# PoE.net
KiCad netlist of a schematic drawn in Altium Designer
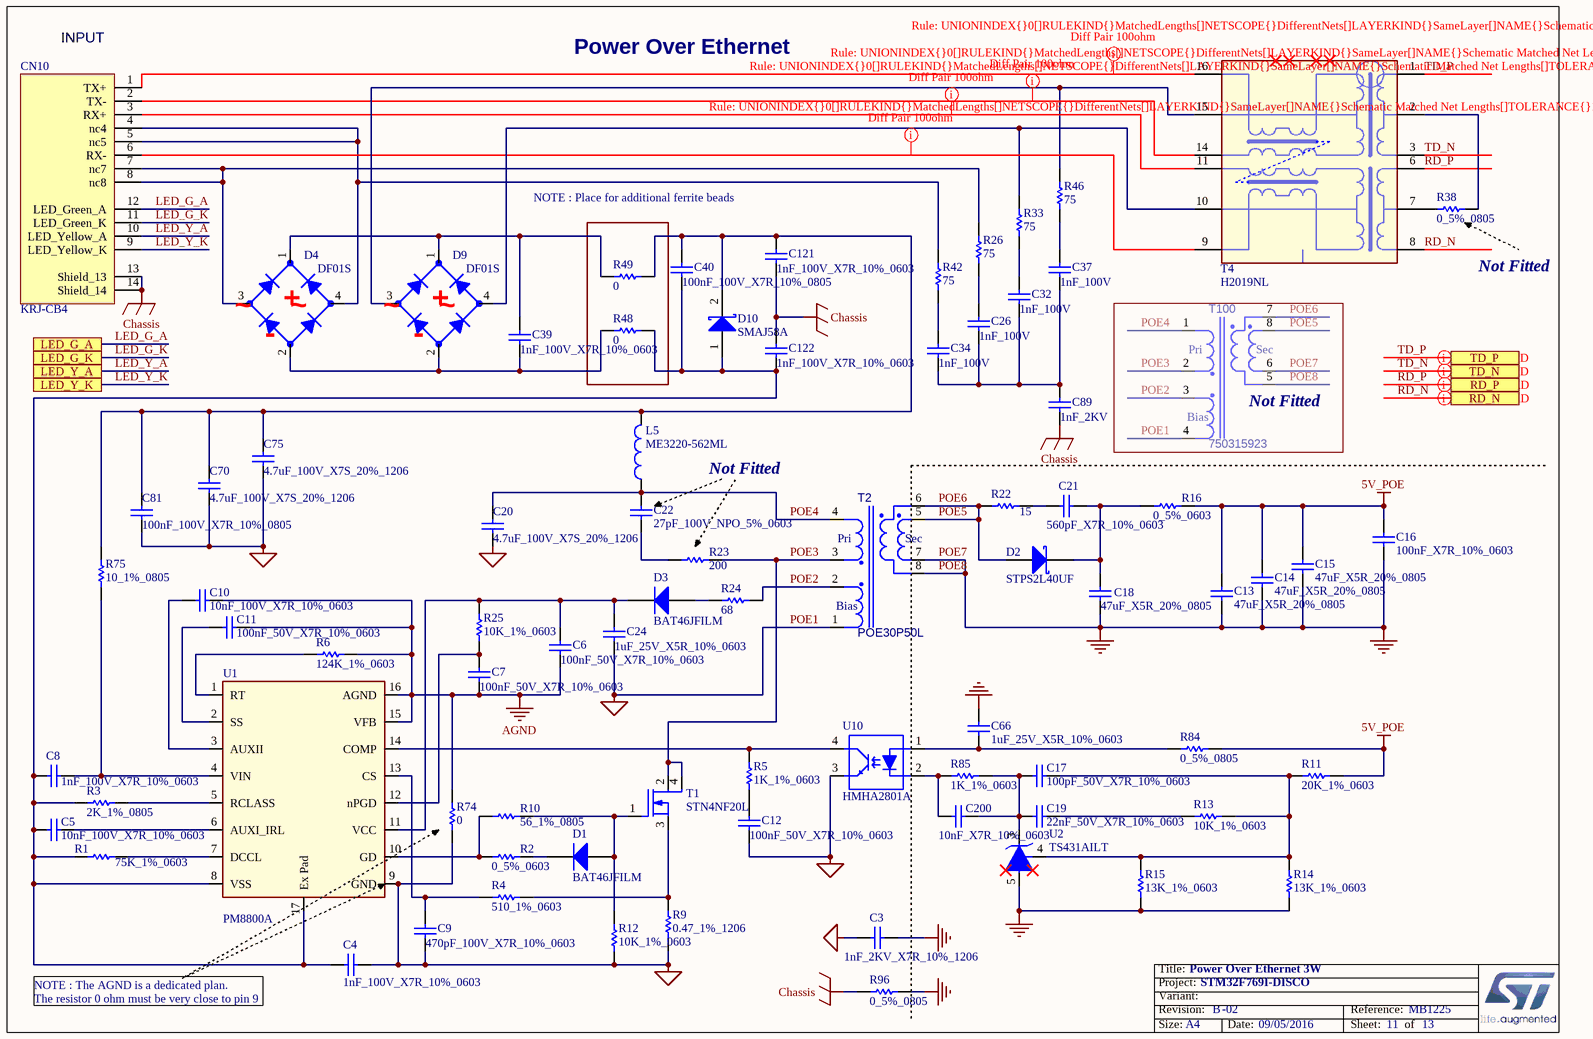
[diagram p0: PoE.SchDoc]

(export (version "E")
  (design (tool "Eeschema 10.0.6"))
  (components
    (comp (ref "C3")
      (value "1nF_2KV_X7R_10%_1206")
      (footprint "1206C")
      (description "Capacitor,1nF,2KV,X7R,10%,1206,YAGEO")
      (libsource (lib "MCD_TOOLS_CAPACITOR") (part "Cap_1nF_2KV_X7R_10%_1206"))
    )
    (comp (ref "C4")
      (value "1nF_100V_X7R_10%_0603")
      (footprint "0603C")
      (description "Capacitor,1nF,100V,X7R,10%,0603,YAGEO")
      (libsource (lib "MCD_TOOLS_CAPACITOR") (part "Cap_1nF_100V_X7R_10%_0603"))
    )
    (comp (ref "C5")
      (value "10nF_100V_X7R_10%_0603")
      (footprint "0603C")
      (description "Capacitor,10nF,100V,X7R,10%,0603,YAGEO")
      (libsource (lib "MCD_TOOLS_CAPACITOR") (part "Cap_10nF_100V_X7R_10%_0603"))
    )
    (comp (ref "C6")
      (value "100nF_50V_X7R_10%_0603")
      (footprint "0603C")
      (description "Capacitor,100nF,50V,X7R,10%,0603,YAGEO")
      (libsource (lib "MCD_TOOLS_CAPACITOR") (part "Cap_100nF_50V_X7R_10%_0603"))
    )
    (comp (ref "C7")
      (value "100nF_50V_X7R_10%_0603")
      (footprint "0603C")
      (description "Capacitor,100nF,50V,X7R,10%,0603,YAGEO")
      (libsource (lib "MCD_TOOLS_CAPACITOR") (part "Cap_100nF_50V_X7R_10%_0603"))
    )
    (comp (ref "C8")
      (value "1nF_100V_X7R_10%_0603")
      (footprint "0603C")
      (description "Capacitor,1nF,100V,X7R,10%,0603,YAGEO")
      (libsource (lib "MCD_TOOLS_CAPACITOR") (part "Cap_1nF_100V_X7R_10%_0603"))
    )
    (comp (ref "C9")
      (value "470pF_100V_X7R_10%_0603")
      (footprint "0603C")
      (description "Capacitor,470pF,100V,X7R,10%,0603,AVX")
      (libsource (lib "MCD_TOOLS_CAPACITOR") (part "Cap_470pF_100V_X7R_10%_0603"))
    )
    (comp (ref "C10")
      (value "10nF_100V_X7R_10%_0603")
      (footprint "0603C")
      (description "Capacitor,10nF,100V,X7R,10%,0603,YAGEO")
      (libsource (lib "MCD_TOOLS_CAPACITOR") (part "Cap_10nF_100V_X7R_10%_0603"))
    )
    (comp (ref "C11")
      (value "100nF_50V_X7R_10%_0603")
      (footprint "0603C")
      (description "Capacitor,100nF,50V,X7R,10%,0603,YAGEO")
      (libsource (lib "MCD_TOOLS_CAPACITOR") (part "Cap_100nF_50V_X7R_10%_0603"))
    )
    (comp (ref "C12")
      (value "100nF_50V_X7R_10%_0603")
      (footprint "0603C")
      (description "Capacitor,100nF,50V,X7R,10%,0603,YAGEO")
      (libsource (lib "MCD_TOOLS_CAPACITOR") (part "Cap_100nF_50V_X7R_10%_0603"))
    )
    (comp (ref "C13")
      (value "47uF_X5R_20%_0805")
      (footprint "0805C")
      (description "Capacitor,47uF,10V,X5R,20%,0805,MURATA")
      (libsource (lib "MCD_TOOLS_CAPACITOR") (part "Cap_47uF_X5R_20%_0805"))
    )
    (comp (ref "C14")
      (value "47uF_X5R_20%_0805")
      (footprint "0805C")
      (description "Capacitor,47uF,10V,X5R,20%,0805,MURATA")
      (libsource (lib "MCD_TOOLS_CAPACITOR") (part "Cap_47uF_X5R_20%_0805"))
    )
    (comp (ref "C15")
      (value "47uF_X5R_20%_0805")
      (footprint "0805C")
      (description "Capacitor,47uF,10V,X5R,20%,0805,MURATA")
      (libsource (lib "MCD_TOOLS_CAPACITOR") (part "Cap_47uF_X5R_20%_0805"))
    )
    (comp (ref "C16")
      (value "100nF_X7R_10%_0603")
      (footprint "0603C")
      (description "Capacitor,100nF,16V,X7R,10%,0603,YAGEO")
      (libsource (lib "MCD_TOOLS_CAPACITOR") (part "Cap_100nF_X7R_10%_0603"))
    )
    (comp (ref "C17")
      (value "100pF_50V_X7R_10%_0603")
      (footprint "0603C")
      (description "Capacitor,100pF,50V,X7R,10%,0603,AVX")
      (libsource (lib "MCD_TOOLS_CAPACITOR") (part "Cap_100pF_50V_X7R_10%_0603"))
    )
    (comp (ref "C18")
      (value "47uF_X5R_20%_0805")
      (footprint "0805C")
      (description "Capacitor,47uF,10V,X5R,20%,0805,MURATA")
      (libsource (lib "MCD_TOOLS_CAPACITOR") (part "Cap_47uF_X5R_20%_0805"))
    )
    (comp (ref "C19")
      (value "22nF_50V_X7R_10%_0603")
      (footprint "0603C")
      (description "Capacitor,22nF,50V,X7R,10%,0603,YAGEO")
      (libsource (lib "MCD_TOOLS_CAPACITOR") (part "Cap_22nF_50V_X7R_10%_0603"))
    )
    (comp (ref "C20")
      (value "4.7uF_100V_X7S_20%_1206")
      (footprint "1206C")
      (description "Capacitor,4.7uF,100V, X7S,20%,1206,AVX")
      (libsource (lib "MCD_TOOLS_CAPACITOR") (part "Cap_4.7uF_100V_X7S_20%_1206"))
    )
    (comp (ref "C21")
      (value "560pF_X7R_10%_0603")
      (footprint "0603C")
      (description "Capacitor,560pF,16V,X7R,10%,0603,AVX")
      (libsource (lib "MCD_TOOLS_CAPACITOR") (part "Cap_560pF_X7R_10%_0603"))
    )
    (comp (ref "C22")
      (value "27pF_100V_NPO_5%_0603")
      (footprint "0603C")
      (description "Capacitor,27pF,100V,NPO,5%,0603,YAGEO")
      (libsource (lib "MCD_TOOLS_CAPACITOR") (part "Cap_27pF_100V_NPO_5%_0603"))
    )
    (comp (ref "C24")
      (value "1uF_25V_X5R_10%_0603")
      (footprint "0603C")
      (description "Capacitor,1uF,25V,X5R,10%,0603,YAGEO")
      (libsource (lib "MCD_TOOLS_CAPACITOR") (part "Cap_1uF_25V_X5R_10%_0603"))
    )
    (comp (ref "C26")
      (value "1nF_100V")
      (footprint "0603C")
      (description "Capacitor,1nF,100V,X7R,10%,0603,YAGEO")
      (libsource (lib "MCD_TOOLS_CAPACITOR") (part "Cap_1nF_100V_X7R_10%_0603"))
    )
    (comp (ref "C32")
      (value "1nF_100V")
      (footprint "0603C")
      (description "Capacitor,1nF,100V,X7R,10%,0603,YAGEO")
      (libsource (lib "MCD_TOOLS_CAPACITOR") (part "Cap_1nF_100V_X7R_10%_0603"))
    )
    (comp (ref "C34")
      (value "1nF_100V")
      (footprint "0603C")
      (description "Capacitor,1nF,100V,X7R,10%,0603,YAGEO")
      (libsource (lib "MCD_TOOLS_CAPACITOR") (part "Cap_1nF_100V_X7R_10%_0603"))
    )
    (comp (ref "C37")
      (value "1nF_100V")
      (footprint "0603C")
      (description "Capacitor,1nF,100V,X7R,10%,0603,YAGEO")
      (libsource (lib "MCD_TOOLS_CAPACITOR") (part "Cap_1nF_100V_X7R_10%_0603"))
    )
    (comp (ref "C39")
      (value "1nF_100V_X7R_10%_0603")
      (footprint "0603C")
      (description "Capacitor,1nF,100V,X7R,10%,0603,YAGEO")
      (libsource (lib "MCD_TOOLS_CAPACITOR") (part "Cap_1nF_100V_X7R_10%_0603"))
    )
    (comp (ref "C40")
      (value "100nF_100V_X7R_10%_0805")
      (footprint "0805C")
      (description "Capacitor,100nF,100V,X7R,10%,0805,TDK")
      (libsource (lib "MCD_TOOLS_CAPACITOR") (part "Cap_100nF_100V_X7R_10%_0805"))
    )
    (comp (ref "C66")
      (value "1uF_25V_X5R_10%_0603")
      (footprint "0603C")
      (description "Capacitor,1uF,25V,X5R,10%,0603,YAGEO")
      (libsource (lib "MCD_TOOLS_CAPACITOR") (part "Cap_1uF_25V_X5R_10%_0603"))
    )
    (comp (ref "C70")
      (value "4.7uF_100V_X7S_20%_1206")
      (footprint "1206C")
      (description "Capacitor,4.7uF,100V, X7S,20%,1206,AVX")
      (libsource (lib "MCD_TOOLS_CAPACITOR") (part "Cap_4.7uF_100V_X7S_20%_1206"))
    )
    (comp (ref "C75")
      (value "4.7uF_100V_X7S_20%_1206")
      (footprint "1206C")
      (description "Capacitor,4.7uF,100V, X7S,20%,1206,AVX")
      (libsource (lib "MCD_TOOLS_CAPACITOR") (part "Cap_4.7uF_100V_X7S_20%_1206"))
    )
    (comp (ref "C81")
      (value "100nF_100V_X7R_10%_0805")
      (footprint "0805C")
      (description "Capacitor,100nF,100V,X7R,10%,0805,TDK")
      (libsource (lib "MCD_TOOLS_CAPACITOR") (part "Cap_100nF_100V_X7R_10%_0805"))
    )
    (comp (ref "C89")
      (value "1nF_2KV")
      (footprint "1206C")
      (description "Capacitor,1nF,2KV,X7R,10%,1206,YAGEO")
      (libsource (lib "MCD_TOOLS_CAPACITOR") (part "Cap_1nF_2KV_X7R_10%_1206"))
    )
    (comp (ref "C121")
      (value "1nF_100V_X7R_10%_0603")
      (footprint "0603C")
      (description "Capacitor,1nF,100V,X7R,10%,0603,YAGEO")
      (libsource (lib "MCD_TOOLS_CAPACITOR") (part "Cap_1nF_100V_X7R_10%_0603"))
    )
    (comp (ref "C122")
      (value "1nF_100V_X7R_10%_0603")
      (footprint "0603C")
      (description "Capacitor,1nF,100V,X7R,10%,0603,YAGEO")
      (libsource (lib "MCD_TOOLS_CAPACITOR") (part "Cap_1nF_100V_X7R_10%_0603"))
    )
    (comp (ref "C200")
      (value "10nF_X7R_10%_0603")
      (footprint "0603C")
      (description "Capacitor,10nF,50V,X7R,10%,0603,YAGEO")
      (libsource (lib "MCD_TOOLS_CAPACITOR") (part "Cap_10nF_X7R_10%_0603"))
    )
    (comp (ref "CN10")
      (value "KRJ-CB4")
      (footprint "RJ45_LED_KRJ-CB4R2GYZNL_EM")
      (description "100 Base-TX (Fast Ethernet)  RJ45 single port (1x1) with LEDS Integrated Connector")
      (libsource (lib "MCD_TOOLS_CONNECTOR") (part "KRJ-CB4"))
    )
    (comp (ref "D1")
      (value "BAT46JFILM")
      (footprint "SOD-323")
      (description "Schottky Single diode(150mA, 100V)")
      (libsource (lib "MCD_TOOLS_MISCELLANEOUS") (part "BAT46JFILM"))
    )
    (comp (ref "D2")
      (value "STPS2L40UF")
      (footprint "SMB")
      (description "Low drop power Schottky rectifier(2A, 40V, 0.34V)")
      (libsource (lib "MCD_TOOLS_MISCELLANEOUS") (part "STPS2L40UF"))
    )
    (comp (ref "D3")
      (value "BAT46JFILM")
      (footprint "SOD-323")
      (description "Schottky Single diode(150mA, 100V)")
      (libsource (lib "MCD_TOOLS_MISCELLANEOUS") (part "BAT46JFILM"))
    )
    (comp (ref "D4")
      (value "DF01S")
      (footprint "DBS101-107G")
      (description "Surface Mount Bridge Rectifiers")
      (libsource (lib "MCD_TOOLS_MISCELLANEOUS") (part "DF01S_SMD"))
    )
    (comp (ref "D9")
      (value "DF01S")
      (footprint "DBS101-107G")
      (description "Surface Mount Bridge Rectifiers")
      (libsource (lib "MCD_TOOLS_MISCELLANEOUS") (part "DF01S_SMD"))
    )
    (comp (ref "D10")
      (value "SMAJ58A")
      (footprint "SMA")
      (description "Transil 400W, VRM=58V")
      (libsource (lib "MCD_TOOLS_MISCELLANEOUS") (part "SMAJ58A"))
    )
    (comp (ref "L5")
      (value "ME3220-562ML")
      (footprint "LSM2_3R2X2R8_H2")
      (description "Power Inductor, 5.6uH, 0.2R, ME3220-562ML, CoilCraft")
      (libsource (lib "MCD_TOOLS_MISCELLANEOUS") (part "ME3220-562ML"))
    )
    (comp (ref "R1")
      (value "75K_1%_0603")
      (footprint "0603R")
      (description "Resistor,75K,0603,1%,YAGEO")
      (libsource (lib "MCD_TOOLS_RESISTOR") (part "Res_75K_1%_0603"))
    )
    (comp (ref "R2")
      (value "0_5%_0603")
      (footprint "0603R-GS")
      (description "Resistor,0,0603,5%,YAGEO")
      (libsource (lib "MCD_TOOLS_RESISTOR") (part "Res_0_5%_0603"))
    )
    (comp (ref "R3")
      (value "2K_1%_0805")
      (footprint "0805R")
      (description "Resistor,2K,0805,1%,YAGEO")
      (libsource (lib "MCD_TOOLS_RESISTOR") (part "Res_2K_1%_0805"))
    )
    (comp (ref "R4")
      (value "510_1%_0603")
      (footprint "0603R")
      (description "Resistor,510,0603,1%,YAGEO")
      (libsource (lib "MCD_TOOLS_RESISTOR") (part "Res_510_1%_0603"))
    )
    (comp (ref "R5")
      (value "1K_1%_0603")
      (footprint "0603R")
      (description "Resistor,1K,0603,1%,YAGEO")
      (libsource (lib "MCD_TOOLS_RESISTOR") (part "Res_1K_1%_0603"))
    )
    (comp (ref "R6")
      (value "124K_1%_0603")
      (footprint "0603R")
      (description "Resistor,124K,0603,1%,YAGEO")
      (libsource (lib "MCD_TOOLS_RESISTOR") (part "Res_124K_1%_0603"))
    )
    (comp (ref "R9")
      (value "0.47_1%_1206")
      (footprint "1206R")
      (description "Resistor,0.47,1206,1%,YAGEO")
      (libsource (lib "MCD_TOOLS_RESISTOR") (part "Res_0.47_1%_1206"))
    )
    (comp (ref "R10")
      (value "56_1%_0805")
      (footprint "0805R")
      (description "Resistor,56,0805,1%,YAGEO")
      (libsource (lib "MCD_TOOLS_RESISTOR") (part "Res_56_1%_0805"))
    )
    (comp (ref "R11")
      (value "20K_1%_0603")
      (footprint "0603R")
      (description "Resistor,20K,0603,1%,YAGEO")
      (libsource (lib "MCD_TOOLS_RESISTOR") (part "Res_20K_1%_0603"))
    )
    (comp (ref "R12")
      (value "10K_1%_0603")
      (footprint "0603R")
      (description "Resistor,10K,0603,1%,YAGEO")
      (libsource (lib "MCD_TOOLS_RESISTOR") (part "Res_10K_1%_0603"))
    )
    (comp (ref "R13")
      (value "10K_1%_0603")
      (footprint "0603R")
      (description "Resistor,10K,0603,1%,YAGEO")
      (libsource (lib "MCD_TOOLS_RESISTOR") (part "Res_10K_1%_0603"))
    )
    (comp (ref "R14")
      (value "13K_1%_0603")
      (footprint "0603R")
      (description "Resistor,13K,0603,1%,YAGEO")
      (libsource (lib "MCD_TOOLS_RESISTOR") (part "Res_13K_1%_0603"))
    )
    (comp (ref "R15")
      (value "13K_1%_0603")
      (footprint "0603R")
      (description "Resistor,13K,0603,1%,YAGEO")
      (libsource (lib "MCD_TOOLS_RESISTOR") (part "Res_13K_1%_0603"))
    )
    (comp (ref "R16")
      (value "0_5%_0603")
      (footprint "0603R-GS")
      (description "Resistor,0,0603,5%,YAGEO")
      (libsource (lib "MCD_TOOLS_RESISTOR") (part "Res_0_5%_0603"))
    )
    (comp (ref "R22")
      (value "15")
      (footprint "0805R")
      (description "Resistor,15,0805,1%,YAGEO")
      (libsource (lib "MCD_TOOLS_RESISTOR") (part "Res_15_1%_0805"))
    )
    (comp (ref "R23")
      (value "200")
      (footprint "1206R")
      (description "Resistor,200,1206,1%,Rohm")
      (libsource (lib "MCD_TOOLS_RESISTOR") (part "Res_200_1%_1206"))
    )
    (comp (ref "R24")
      (value "68")
      (footprint "0805R")
      (description "Resistor,68,0805,1%,YAGEO")
      (libsource (lib "MCD_TOOLS_RESISTOR") (part "Res_68_1%_0805"))
    )
    (comp (ref "R25")
      (value "10K_1%_0603")
      (footprint "0603R")
      (description "Resistor,10K,0603,1%,YAGEO")
      (libsource (lib "MCD_TOOLS_RESISTOR") (part "Res_10K_1%_0603"))
    )
    (comp (ref "R26")
      (value "75")
      (footprint "0805R")
      (description "Resistor,75,0805,1%,YAGEO")
      (libsource (lib "MCD_TOOLS_RESISTOR") (part "Res_75_1%_0805"))
    )
    (comp (ref "R33")
      (value "75")
      (footprint "0805R")
      (description "Resistor,75,0805,1%,YAGEO")
      (libsource (lib "MCD_TOOLS_RESISTOR") (part "Res_75_1%_0805"))
    )
    (comp (ref "R38")
      (value "0_5%_0805")
      (footprint "0805R")
      (description "Resistor,0,0805,5%,YAGEO")
      (libsource (lib "MCD_TOOLS_RESISTOR") (part "Res_0_5%_0805"))
    )
    (comp (ref "R42")
      (value "75")
      (footprint "0805R")
      (description "Resistor,75,0805,1%,YAGEO")
      (libsource (lib "MCD_TOOLS_RESISTOR") (part "Res_75_1%_0805"))
    )
    (comp (ref "R46")
      (value "75")
      (footprint "0805R")
      (description "Resistor,75,0805,1%,YAGEO")
      (libsource (lib "MCD_TOOLS_RESISTOR") (part "Res_75_1%_0805"))
    )
    (comp (ref "R48")
      (value "0")
      (footprint "0805R")
      (description "Resistor,0,0805,5%,YAGEO")
      (libsource (lib "MCD_TOOLS_RESISTOR") (part "Res_0_5%_0805"))
    )
    (comp (ref "R49")
      (value "0")
      (footprint "0805R")
      (description "Resistor,0,0805,5%,YAGEO")
      (libsource (lib "MCD_TOOLS_RESISTOR") (part "Res_0_5%_0805"))
    )
    (comp (ref "R74")
      (value "0")
      (footprint "0603R-GS")
      (description "Resistor,0,0603,5%,YAGEO")
      (libsource (lib "MCD_TOOLS_RESISTOR") (part "Res_0_5%_0603"))
    )
    (comp (ref "R75")
      (value "10_1%_0805")
      (footprint "0805R")
      (description "Resistor,10,0805,1%,Stackpole,1/4W")
      (libsource (lib "MCD_TOOLS_RESISTOR") (part "Res_10_1%_0805"))
    )
    (comp (ref "R84")
      (value "0_5%_0805")
      (footprint "0805R")
      (description "Resistor,0,0805,5%,YAGEO")
      (libsource (lib "MCD_TOOLS_RESISTOR") (part "Res_0_5%_0805"))
    )
    (comp (ref "R85")
      (value "1K_1%_0603")
      (footprint "0603R")
      (description "Resistor,1K,0603,1%,YAGEO")
      (libsource (lib "MCD_TOOLS_RESISTOR") (part "Res_1K_1%_0603"))
    )
    (comp (ref "R96")
      (value "0_5%_0805")
      (footprint "0805R")
      (description "Resistor,0,0805,5%,YAGEO")
      (libsource (lib "MCD_TOOLS_RESISTOR") (part "Res_0_5%_0805"))
    )
    (comp (ref "T1")
      (value "STN4NF20L")
      (footprint "SOT-223")
      (description "N-channel 200 V, 1.1ohm, 1 A, low gate charge STripFET II, Power MOSFET")
      (libsource (lib "MCD_TOOLS_MISCELLANEOUS") (part "STN4NF20L"))
    )
    (comp (ref "T2")
      (value "POE30P50L")
      (footprint "TF_10R9X13R2-12R2X14R4_CPT")
      (description "Flyback Transformers for 3 Watt, PoE applications, CoilCraft Cyntec")
      (fields (field (name "PROVIDED") "Sub Co"))
      (libsource (lib "MCD_TOOLS_MISCELLANEOUS") (part "POE30P_C"))
    )
    (comp (ref "T4")
      (value "H2019NL")
      (footprint "TF_16SM_12R7X9R65")
      (description "10/100BASE-TX VoIP Magnetics Modules, Data Transformer")
      (libsource (lib "MCD_TOOLS_MISCELLANEOUS") (part "H2019"))
    )
    (comp (ref "T100")
      (value "750315923")
      (footprint "TF_8SM_12R04X12R85")
      (description "Flyback Transformers for 3 Watt, PoE applications, Wurth")
      (fields (field (name "PROVIDED") "Sub Co"))
      (libsource (lib "MCD_TOOLS_MISCELLANEOUS") (part "POE30P_W"))
    )
    (comp (ref "U1")
      (value "PM8800A")
      (footprint "TSSOP16_0R65_5x6R4_TP")
      (fields (field (name "PROVIDED") "STM"))
      (libsource (lib "MCD_TOOLS_MISCELLANEOUS") (part "PM8800A"))
    )
    (comp (ref "U2")
      (value "TS431AILT")
      (footprint "SOT23-5")
      (description "Low voltage adjustable shunt reference")
      (libsource (lib "MCD_TOOLS_MISCELLANEOUS") (part "TS431AILT"))
    )
    (comp (ref "U10")
      (value "HMHA2801A")
      (footprint "PC_4SM_1R27_2R5X6R8")
      (description "OPTOISOLATOR 3.7KV TRANSISTOR 4SMD")
      (libsource (lib "MCD_TOOLS_MISCELLANEOUS") (part "HMHA2801A"))
    )
  )
  (nets
    (net (code "1") (name "/LED_G_A") (class "Default")
      (node (ref "CN10") (pin "12") (pinfunction "LED_Green_A_12") (pintype "passive"))
    )
    (net (code "2") (name "/LED_G_K") (class "Default")
      (node (ref "CN10") (pin "11") (pinfunction "LED_Green_K_11") (pintype "passive"))
    )
    (net (code "3") (name "/LED_Y_A") (class "Default")
      (node (ref "CN10") (pin "10") (pinfunction "LED_Yellow_A_10") (pintype "passive"))
    )
    (net (code "4") (name "/LED_Y_K") (class "Default")
      (node (ref "CN10") (pin "9") (pinfunction "LED_Yellow_K_9") (pintype "passive"))
    )
    (net (code "5") (name "/POE2") (class "Default")
      (node (ref "R24") (pin "2") (pinfunction "2_2") (pintype "passive"))
      (node (ref "T100") (pin "3") (pinfunction "3_3") (pintype "passive"))
      (node (ref "T2") (pin "2") (pinfunction "2_2") (pintype "passive"))
    )
    (net (code "6") (name "/POE3") (class "Default")
      (node (ref "R23") (pin "2") (pinfunction "2_2") (pintype "passive"))
      (node (ref "T1") (pin "2") (pinfunction "D_2") (pintype "passive"))
      (node (ref "T1") (pin "4") (pinfunction "D_4") (pintype "passive"))
      (node (ref "T100") (pin "2") (pinfunction "2_2") (pintype "passive"))
      (node (ref "T2") (pin "3") (pinfunction "3_3") (pintype "passive"))
    )
    (net (code "7") (name "/POE4") (class "Default")
      (node (ref "C20") (pin "2") (pinfunction "2_2") (pintype "passive"))
      (node (ref "C22") (pin "2") (pinfunction "2_2") (pintype "passive"))
      (node (ref "L5") (pin "1") (pinfunction "1_1") (pintype "passive"))
      (node (ref "T100") (pin "1") (pinfunction "1_1") (pintype "passive"))
      (node (ref "T2") (pin "4") (pinfunction "4_4") (pintype "passive"))
    )
    (net (code "8") (name "/POE5") (class "Default")
      (node (ref "D2") (pin "1") (pinfunction "A_1") (pintype "passive"))
      (node (ref "R22") (pin "1") (pinfunction "1_1") (pintype "passive"))
      (node (ref "T100") (pin "7") (pinfunction "7_7") (pintype "passive"))
      (node (ref "T100") (pin "8") (pinfunction "8_8") (pintype "passive"))
      (node (ref "T2") (pin "5") (pinfunction "5_5") (pintype "passive"))
      (node (ref "T2") (pin "6") (pinfunction "6_6") (pintype "passive"))
    )
    (net (code "9") (name "/RD_N") (class "Default")
      (node (ref "T4") (pin "8") (pinfunction "rd-_8") (pintype "passive"))
    )
    (net (code "10") (name "/RD_P") (class "Default")
      (node (ref "T4") (pin "6") (pinfunction "rd+_6") (pintype "passive"))
    )
    (net (code "11") (name "/TD_N") (class "Default")
      (node (ref "T4") (pin "3") (pinfunction "td-_3") (pintype "passive"))
    )
    (net (code "12") (name "/TD_P") (class "Default")
      (node (ref "T4") (pin "1") (pinfunction "td+_1") (pintype "passive"))
    )
    (net (code "13") (name "5V_POE") (class "Default")
      (node (ref "C13") (pin "2") (pinfunction "2_2") (pintype "passive"))
      (node (ref "C14") (pin "2") (pinfunction "2_2") (pintype "passive"))
      (node (ref "C15") (pin "2") (pinfunction "2_2") (pintype "passive"))
      (node (ref "C16") (pin "2") (pinfunction "2_2") (pintype "passive"))
      (node (ref "R11") (pin "2") (pinfunction "2_2") (pintype "passive"))
      (node (ref "R16") (pin "2") (pinfunction "2_2") (pintype "passive"))
      (node (ref "R84") (pin "2") (pinfunction "2_2") (pintype "passive"))
    )
    (net (code "14") (name "AGND") (class "Default")
      (node (ref "C10") (pin "2") (pinfunction "2_2") (pintype "passive"))
      (node (ref "C11") (pin "2") (pinfunction "2_2") (pintype "passive"))
      (node (ref "C6") (pin "1") (pinfunction "1_1") (pintype "passive"))
      (node (ref "C7") (pin "1") (pinfunction "1_1") (pintype "passive"))
      (node (ref "R6") (pin "2") (pinfunction "2_2") (pintype "passive"))
      (node (ref "R74") (pin "2") (pinfunction "2_2") (pintype "passive"))
      (node (ref "U1") (pin "15") (pinfunction "VFB_15") (pintype "passive"))
      (node (ref "U1") (pin "16") (pinfunction "AGND_16") (pintype "passive"))
    )
    (net (code "15") (name "Chassis") (class "Default")
      (node (ref "C121") (pin "1") (pinfunction "1_1") (pintype "passive"))
      (node (ref "C122") (pin "2") (pinfunction "2_2") (pintype "passive"))
      (node (ref "C89") (pin "1") (pinfunction "1_1") (pintype "passive"))
      (node (ref "CN10") (pin "13") (pinfunction "Shield_13_13") (pintype "passive"))
      (node (ref "CN10") (pin "14") (pinfunction "Shield_14_14") (pintype "passive"))
      (node (ref "R96") (pin "1") (pinfunction "1_1") (pintype "passive"))
    )
    (net (code "16") (name "GND") (class "Default")
      (node (ref "C13") (pin "1") (pinfunction "1_1") (pintype "passive"))
      (node (ref "C14") (pin "1") (pinfunction "1_1") (pintype "passive"))
      (node (ref "C15") (pin "1") (pinfunction "1_1") (pintype "passive"))
      (node (ref "C16") (pin "1") (pinfunction "1_1") (pintype "passive"))
      (node (ref "C18") (pin "1") (pinfunction "1_1") (pintype "passive"))
      (node (ref "C3") (pin "2") (pinfunction "2_2") (pintype "passive"))
      (node (ref "C66") (pin "2") (pinfunction "2_2") (pintype "passive"))
      (node (ref "R14") (pin "1") (pinfunction "1_1") (pintype "passive"))
      (node (ref "R15") (pin "1") (pinfunction "1_1") (pintype "passive"))
      (node (ref "R96") (pin "2") (pinfunction "2_2") (pintype "passive"))
      (node (ref "T100") (pin "5") (pinfunction "5_5") (pintype "passive"))
      (node (ref "T100") (pin "6") (pinfunction "6_6") (pintype "passive"))
      (node (ref "T2") (pin "7") (pinfunction "7_7") (pintype "passive"))
      (node (ref "T2") (pin "8") (pinfunction "8_8") (pintype "passive"))
      (node (ref "U2") (pin "5") (pinfunction "A_5") (pintype "passive"))
    )
    (net (code "17") (name "GND_POWER_IN") (class "Default")
      (node (ref "C12") (pin "1") (pinfunction "1_1") (pintype "passive"))
      (node (ref "C20") (pin "1") (pinfunction "1_1") (pintype "passive"))
      (node (ref "C24") (pin "1") (pinfunction "1_1") (pintype "passive"))
      (node (ref "C3") (pin "1") (pinfunction "1_1") (pintype "passive"))
      (node (ref "C4") (pin "2") (pinfunction "2_2") (pintype "passive"))
      (node (ref "C70") (pin "1") (pinfunction "1_1") (pintype "passive"))
      (node (ref "C75") (pin "1") (pinfunction "1_1") (pintype "passive"))
      (node (ref "C81") (pin "1") (pinfunction "1_1") (pintype "passive"))
      (node (ref "C9") (pin "1") (pinfunction "1_1") (pintype "passive"))
      (node (ref "R12") (pin "1") (pinfunction "1_1") (pintype "passive"))
      (node (ref "R74") (pin "1") (pinfunction "1_1") (pintype "passive"))
      (node (ref "R9") (pin "1") (pinfunction "1_1") (pintype "passive"))
      (node (ref "T100") (pin "4") (pinfunction "4_4") (pintype "passive"))
      (node (ref "T2") (pin "1") (pinfunction "1_1") (pintype "passive"))
      (node (ref "U1") (pin "9") (pinfunction "GND_9") (pintype "passive"))
      (node (ref "U10") (pin "3") (pinfunction "Emitter_3") (pintype "passive"))
    )
    (net (code "18") (name "Net-(C12-Pad2)") (class "Default")
      (node (ref "C12") (pin "2") (pinfunction "2_2") (pintype "passive"))
      (node (ref "R5") (pin "1") (pinfunction "1_1") (pintype "passive"))
    )
    (net (code "19") (name "Net-(C19-Pad2)") (class "Default")
      (node (ref "C19") (pin "2") (pinfunction "2_2") (pintype "passive"))
      (node (ref "R13") (pin "1") (pinfunction "1_1") (pintype "passive"))
    )
    (net (code "20") (name "Net-(C21-Pad1)") (class "Default")
      (node (ref "C21") (pin "1") (pinfunction "1_1") (pintype "passive"))
      (node (ref "R22") (pin "2") (pinfunction "2_2") (pintype "passive"))
    )
    (net (code "21") (name "Net-(C22-Pad1)") (class "Default")
      (node (ref "C22") (pin "1") (pinfunction "1_1") (pintype "passive"))
      (node (ref "R23") (pin "1") (pinfunction "1_1") (pintype "passive"))
    )
    (net (code "22") (name "Net-(C26-Pad1)") (class "Default")
      (node (ref "C26") (pin "1") (pinfunction "1_1") (pintype "passive"))
      (node (ref "C32") (pin "1") (pinfunction "1_1") (pintype "passive"))
      (node (ref "C34") (pin "1") (pinfunction "1_1") (pintype "passive"))
      (node (ref "C37") (pin "1") (pinfunction "1_1") (pintype "passive"))
      (node (ref "C89") (pin "2") (pinfunction "2_2") (pintype "passive"))
    )
    (net (code "23") (name "Net-(C26-Pad2)") (class "Default")
      (node (ref "C26") (pin "2") (pinfunction "2_2") (pintype "passive"))
      (node (ref "R26") (pin "1") (pinfunction "1_1") (pintype "passive"))
    )
    (net (code "24") (name "Net-(C32-Pad2)") (class "Default")
      (node (ref "C32") (pin "2") (pinfunction "2_2") (pintype "passive"))
      (node (ref "R33") (pin "1") (pinfunction "1_1") (pintype "passive"))
    )
    (net (code "25") (name "Net-(C34-Pad2)") (class "Default")
      (node (ref "C34") (pin "2") (pinfunction "2_2") (pintype "passive"))
      (node (ref "R42") (pin "1") (pinfunction "1_1") (pintype "passive"))
    )
    (net (code "26") (name "Net-(C37-Pad2)") (class "Default")
      (node (ref "C37") (pin "2") (pinfunction "2_2") (pintype "passive"))
      (node (ref "R46") (pin "1") (pinfunction "1_1") (pintype "passive"))
    )
    (net (code "27") (name "Net-(CN10-RX+)") (class "Default")
      (node (ref "CN10") (pin "3") (pinfunction "RX+_3") (pintype "passive"))
      (node (ref "T4") (pin "11") (pinfunction "rx1+_11") (pintype "passive"))
    )
    (net (code "28") (name "Net-(CN10-RX-)") (class "Default")
      (node (ref "CN10") (pin "6") (pinfunction "RX-_6") (pintype "passive"))
      (node (ref "T4") (pin "9") (pinfunction "rx-_9") (pintype "passive"))
    )
    (net (code "29") (name "Net-(CN10-TX+)") (class "Default")
      (node (ref "CN10") (pin "1") (pinfunction "TX+_1") (pintype "passive"))
      (node (ref "T4") (pin "16") (pinfunction "tx1+_16") (pintype "passive"))
    )
    (net (code "30") (name "Net-(CN10-TX-)") (class "Default")
      (node (ref "CN10") (pin "2") (pinfunction "TX-_2") (pintype "passive"))
      (node (ref "T4") (pin "14") (pinfunction "tx1-_14") (pintype "passive"))
    )
    (net (code "31") (name "Net-(CN10-nc4)") (class "Default")
      (node (ref "CN10") (pin "4") (pinfunction "nc4_4") (pintype "passive"))
      (node (ref "CN10") (pin "5") (pinfunction "nc5_5") (pintype "passive"))
      (node (ref "D4") (pin "4") (pinfunction "AC_IN_1_4") (pintype "passive"))
      (node (ref "R42") (pin "2") (pinfunction "2_2") (pintype "passive"))
    )
    (net (code "32") (name "Net-(CN10-nc7)") (class "Default")
      (node (ref "CN10") (pin "7") (pinfunction "nc7_7") (pintype "passive"))
      (node (ref "CN10") (pin "8") (pinfunction "nc8_8") (pintype "passive"))
      (node (ref "D4") (pin "3") (pinfunction "AC_IN_2_3") (pintype "passive"))
      (node (ref "R26") (pin "2") (pinfunction "2_2") (pintype "passive"))
    )
    (net (code "33") (name "Net-(D1-A)") (class "Default")
      (node (ref "D1") (pin "1") (pinfunction "A_1") (pintype "passive"))
      (node (ref "R10") (pin "2") (pinfunction "2_2") (pintype "passive"))
      (node (ref "R12") (pin "2") (pinfunction "2_2") (pintype "passive"))
      (node (ref "T1") (pin "1") (pinfunction "G_1") (pintype "passive"))
    )
    (net (code "34") (name "Net-(D1-K)") (class "Default")
      (node (ref "D1") (pin "2") (pinfunction "K_2") (pintype "passive"))
      (node (ref "R2") (pin "2") (pinfunction "2_2") (pintype "passive"))
    )
    (net (code "35") (name "Net-(D2-K)") (class "Default")
      (node (ref "C18") (pin "2") (pinfunction "2_2") (pintype "passive"))
      (node (ref "C21") (pin "2") (pinfunction "2_2") (pintype "passive"))
      (node (ref "D2") (pin "2") (pinfunction "K_2") (pintype "passive"))
      (node (ref "R16") (pin "1") (pinfunction "1_1") (pintype "passive"))
    )
    (net (code "36") (name "Net-(D3-A)") (class "Default")
      (node (ref "D3") (pin "1") (pinfunction "A_1") (pintype "passive"))
      (node (ref "R24") (pin "1") (pinfunction "1_1") (pintype "passive"))
    )
    (net (code "37") (name "Net-(D3-K)") (class "Default")
      (node (ref "C24") (pin "2") (pinfunction "2_2") (pintype "passive"))
      (node (ref "C6") (pin "2") (pinfunction "2_2") (pintype "passive"))
      (node (ref "D3") (pin "2") (pinfunction "K_2") (pintype "passive"))
      (node (ref "R25") (pin "2") (pinfunction "2_2") (pintype "passive"))
      (node (ref "U1") (pin "11") (pinfunction "VCC_11") (pintype "passive"))
    )
    (net (code "38") (name "Net-(D4-DC_OUT_MINUS)") (class "Default")
      (node (ref "C39") (pin "1") (pinfunction "1_1") (pintype "passive"))
      (node (ref "D4") (pin "2") (pinfunction "DC_OUT_MINUS_2") (pintype "passive"))
      (node (ref "D9") (pin "2") (pinfunction "DC_OUT_MINUS_2") (pintype "passive"))
      (node (ref "R48") (pin "1") (pinfunction "1_1") (pintype "passive"))
    )
    (net (code "39") (name "Net-(D4-DC_OUT_PLUS)") (class "Default")
      (node (ref "C39") (pin "2") (pinfunction "2_2") (pintype "passive"))
      (node (ref "D4") (pin "1") (pinfunction "DC_OUT_PLUS_1") (pintype "passive"))
      (node (ref "D9") (pin "1") (pinfunction "DC_OUT_PLUS_1") (pintype "passive"))
      (node (ref "R49") (pin "1") (pinfunction "1_1") (pintype "passive"))
    )
    (net (code "40") (name "Net-(D9-AC_IN_1)") (class "Default")
      (node (ref "D9") (pin "4") (pinfunction "AC_IN_1_4") (pintype "passive"))
      (node (ref "R33") (pin "2") (pinfunction "2_2") (pintype "passive"))
      (node (ref "T4") (pin "10") (pinfunction "rxct_10") (pintype "passive"))
    )
    (net (code "41") (name "Net-(D9-AC_IN_2)") (class "Default")
      (node (ref "D9") (pin "3") (pinfunction "AC_IN_2_3") (pintype "passive"))
      (node (ref "R46") (pin "2") (pinfunction "2_2") (pintype "passive"))
      (node (ref "T4") (pin "15") (pinfunction "txct_15") (pintype "passive"))
    )
    (net (code "42") (name "Net-(D10-A)") (class "Default")
      (node (ref "C122") (pin "1") (pinfunction "1_1") (pintype "passive"))
      (node (ref "C4") (pin "1") (pinfunction "1_1") (pintype "passive"))
      (node (ref "C40") (pin "1") (pinfunction "1_1") (pintype "passive"))
      (node (ref "C5") (pin "1") (pinfunction "1_1") (pintype "passive"))
      (node (ref "C8") (pin "1") (pinfunction "1_1") (pintype "passive"))
      (node (ref "D10") (pin "1") (pinfunction "A_1") (pintype "passive"))
      (node (ref "R1") (pin "1") (pinfunction "1_1") (pintype "passive"))
      (node (ref "R3") (pin "1") (pinfunction "1_1") (pintype "passive"))
      (node (ref "R48") (pin "2") (pinfunction "2_2") (pintype "passive"))
      (node (ref "U1") (pin "17") (pinfunction "Ex_Pad_17") (pintype "passive"))
      (node (ref "U1") (pin "8") (pinfunction "VSS_8") (pintype "passive"))
    )
    (net (code "43") (name "Net-(D10-K)") (class "Default")
      (node (ref "C121") (pin "2") (pinfunction "2_2") (pintype "passive"))
      (node (ref "C40") (pin "2") (pinfunction "2_2") (pintype "passive"))
      (node (ref "C70") (pin "2") (pinfunction "2_2") (pintype "passive"))
      (node (ref "C75") (pin "2") (pinfunction "2_2") (pintype "passive"))
      (node (ref "C81") (pin "2") (pinfunction "2_2") (pintype "passive"))
      (node (ref "D10") (pin "2") (pinfunction "K_2") (pintype "passive"))
      (node (ref "L5") (pin "2") (pinfunction "2_2") (pintype "passive"))
      (node (ref "R49") (pin "2") (pinfunction "2_2") (pintype "passive"))
      (node (ref "R75") (pin "2") (pinfunction "2_2") (pintype "passive"))
    )
    (net (code "44") (name "Net-(T1-S)") (class "Default")
      (node (ref "R4") (pin "2") (pinfunction "2_2") (pintype "passive"))
      (node (ref "R9") (pin "2") (pinfunction "2_2") (pintype "passive"))
      (node (ref "T1") (pin "3") (pinfunction "S_3") (pintype "passive"))
    )
    (net (code "45") (name "Net-(T4-rct)") (class "Default")
      (node (ref "R38") (pin "1") (pinfunction "1_1") (pintype "passive"))
      (node (ref "T4") (pin "7") (pinfunction "rct_7") (pintype "passive"))
    )
    (net (code "46") (name "Net-(T4-tct)") (class "Default")
      (node (ref "R38") (pin "2") (pinfunction "2_2") (pintype "passive"))
      (node (ref "T4") (pin "2") (pinfunction "tct_2") (pintype "passive"))
    )
    (net (code "47") (name "Net-(U1-AUXII)") (class "Default")
      (node (ref "C10") (pin "1") (pinfunction "1_1") (pintype "passive"))
      (node (ref "U1") (pin "3") (pinfunction "AUXII_3") (pintype "passive"))
    )
    (net (code "48") (name "Net-(U1-AUXI_IRL)") (class "Default")
      (node (ref "C5") (pin "2") (pinfunction "2_2") (pintype "passive"))
      (node (ref "U1") (pin "6") (pinfunction "AUXI_IRL_6") (pintype "passive"))
    )
    (net (code "49") (name "Net-(U1-COMP)") (class "Default")
      (node (ref "R5") (pin "2") (pinfunction "2_2") (pintype "passive"))
      (node (ref "U1") (pin "14") (pinfunction "COMP_14") (pintype "passive"))
      (node (ref "U10") (pin "4") (pinfunction "Collector_4") (pintype "passive"))
    )
    (net (code "50") (name "Net-(U1-CS)") (class "Default")
      (node (ref "C9") (pin "2") (pinfunction "2_2") (pintype "passive"))
      (node (ref "R4") (pin "1") (pinfunction "1_1") (pintype "passive"))
      (node (ref "U1") (pin "13") (pinfunction "CS_13") (pintype "passive"))
    )
    (net (code "51") (name "Net-(U1-DCCL)") (class "Default")
      (node (ref "R1") (pin "2") (pinfunction "2_2") (pintype "passive"))
      (node (ref "U1") (pin "7") (pinfunction "DCCL_7") (pintype "passive"))
    )
    (net (code "52") (name "Net-(U1-GD)") (class "Default")
      (node (ref "R10") (pin "1") (pinfunction "1_1") (pintype "passive"))
      (node (ref "R2") (pin "1") (pinfunction "1_1") (pintype "passive"))
      (node (ref "U1") (pin "10") (pinfunction "GD_10") (pintype "passive"))
    )
    (net (code "53") (name "Net-(U1-RCLASS)") (class "Default")
      (node (ref "R3") (pin "2") (pinfunction "2_2") (pintype "passive"))
      (node (ref "U1") (pin "5") (pinfunction "RCLASS_5") (pintype "passive"))
    )
    (net (code "54") (name "Net-(U1-RT)") (class "Default")
      (node (ref "R6") (pin "1") (pinfunction "1_1") (pintype "passive"))
      (node (ref "U1") (pin "1") (pinfunction "RT_1") (pintype "passive"))
    )
    (net (code "55") (name "Net-(U1-SS)") (class "Default")
      (node (ref "C11") (pin "1") (pinfunction "1_1") (pintype "passive"))
      (node (ref "U1") (pin "2") (pinfunction "SS_2") (pintype "passive"))
    )
    (net (code "56") (name "Net-(U1-VIN)") (class "Default")
      (node (ref "C8") (pin "2") (pinfunction "2_2") (pintype "passive"))
      (node (ref "R75") (pin "1") (pinfunction "1_1") (pintype "passive"))
      (node (ref "U1") (pin "4") (pinfunction "VIN_4") (pintype "passive"))
    )
    (net (code "57") (name "Net-(U1-nPGD)") (class "Default")
      (node (ref "C7") (pin "2") (pinfunction "2_2") (pintype "passive"))
      (node (ref "R25") (pin "1") (pinfunction "1_1") (pintype "passive"))
      (node (ref "U1") (pin "12") (pinfunction "nPGD_12") (pintype "passive"))
    )
    (net (code "58") (name "Net-(U2-K)") (class "Default")
      (node (ref "C17") (pin "1") (pinfunction "1_1") (pintype "passive"))
      (node (ref "C19") (pin "1") (pinfunction "1_1") (pintype "passive"))
      (node (ref "C200") (pin "2") (pinfunction "2_2") (pintype "passive"))
      (node (ref "R85") (pin "2") (pinfunction "2_2") (pintype "passive"))
      (node (ref "U2") (pin "3") (pinfunction "K_3") (pintype "passive"))
    )
    (net (code "59") (name "Net-(U2-REF)") (class "Default")
      (node (ref "C17") (pin "2") (pinfunction "2_2") (pintype "passive"))
      (node (ref "R11") (pin "1") (pinfunction "1_1") (pintype "passive"))
      (node (ref "R13") (pin "2") (pinfunction "2_2") (pintype "passive"))
      (node (ref "R14") (pin "2") (pinfunction "2_2") (pintype "passive"))
      (node (ref "R15") (pin "2") (pinfunction "2_2") (pintype "passive"))
      (node (ref "U2") (pin "4") (pinfunction "REF_4") (pintype "passive"))
    )
    (net (code "60") (name "Net-(U10-Anode)") (class "Default")
      (node (ref "C66") (pin "1") (pinfunction "1_1") (pintype "passive"))
      (node (ref "R84") (pin "1") (pinfunction "1_1") (pintype "passive"))
      (node (ref "U10") (pin "1") (pinfunction "Anode_1") (pintype "passive"))
    )
    (net (code "61") (name "Net-(U10-B)") (class "Default")
      (node (ref "C200") (pin "1") (pinfunction "1_1") (pintype "passive"))
      (node (ref "R85") (pin "1") (pinfunction "1_1") (pintype "passive"))
      (node (ref "U10") (pin "2") (pinfunction "B_2") (pintype "passive"))
    )
    (net (code "62") (name "unconnected-(T4-nc_4-Pad4)") (class "Default")
      (node (ref "T4") (pin "4") (pinfunction "nc_4_4") (pintype "passive+no_connect"))
    )
    (net (code "63") (name "unconnected-(T4-nc_5-Pad5)") (class "Default")
      (node (ref "T4") (pin "5") (pinfunction "nc_5_5") (pintype "passive+no_connect"))
    )
    (net (code "64") (name "unconnected-(T4-nc_12-Pad12)") (class "Default")
      (node (ref "T4") (pin "12") (pinfunction "nc_12_12") (pintype "passive+no_connect"))
    )
    (net (code "65") (name "unconnected-(T4-nc_13-Pad13)") (class "Default")
      (node (ref "T4") (pin "13") (pinfunction "nc_13_13") (pintype "passive+no_connect"))
    )
    (net (code "66") (name "unconnected-(U2-nc_1-Pad1)") (class "Default")
      (node (ref "U2") (pin "1") (pinfunction "nc_1_1") (pintype "passive+no_connect"))
    )
    (net (code "67") (name "unconnected-(U2-nc_2-Pad2)") (class "Default")
      (node (ref "U2") (pin "2") (pinfunction "nc_2_2") (pintype "passive+no_connect"))
    )
  )
)
